# 2_TB6612_3_schdoc.net
KiCad netlist of a schematic drawn in Altium Designer
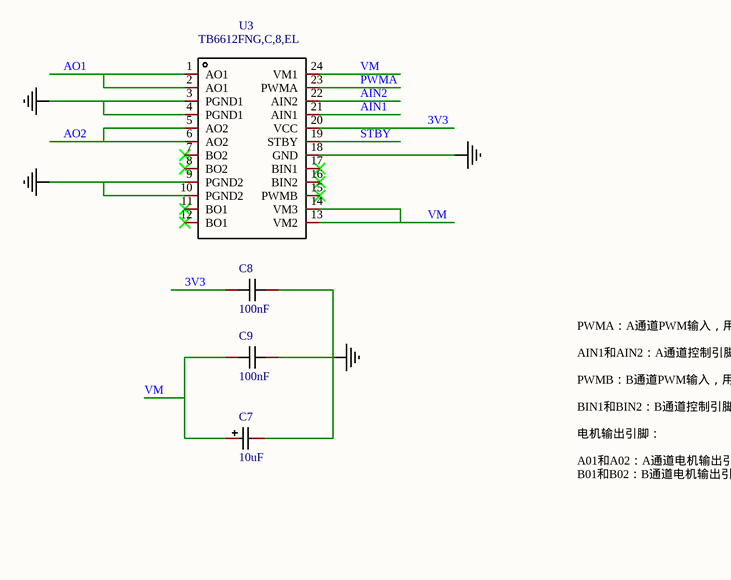
[diagram p0: 2_TB6612（3）.schdoc.schdoc]

(export (version "E")
  (design (tool "Eeschema 10.0.6"))
  (components
    (comp (ref "C7")
      (value "10uF")
      (fields
        (field (name "NAME") "10uF")
        (field (name "MANUFACTURER") "Kyocera AVX")
        (field (name "MANUFACTURER PART") "TAJB106K025RNJ")
        (field (name "TOLERANCE") "±10%")
      )
      (libsource (lib "altium-import") (part "root_2_TAJB106K025RNJ_"))
    )
    (comp (ref "C8")
      (value "100nF")
      (fields (field (name "NAME") "100nF"))
      (libsource (lib "altium-import") (part "root_0_CAP_0603_"))
    )
    (comp (ref "C9")
      (value "100nF")
      (fields (field (name "NAME") "100nF"))
      (libsource (lib "altium-import") (part "root_0_CAP_0603_"))
    )
    (comp (ref "U3")
      (value "TB6612FNG,C,8,EL")
      (description "驱动电机类型:有刷直流电机;电源电压:2.7V~5.5V;输出电流:1A;接口:并行;")
      (fields (field (name "NAME") "TB6612FNG,C,8,EL") (field (name "MANUFACTURER") "TOSHIBA(东芝)"))
      (libsource (lib "altium-import") (part "root_0_TB6612FNG,C,8,EL_"))
    )
  )
  (nets
    (net (code "1") (name "/3V3") (class "Default")
      (node (ref "C8") (pin "1") (pinfunction "1_1") (pintype "passive"))
      (node (ref "U3") (pin "20") (pinfunction "VCC_20") (pintype "passive"))
    )
    (net (code "2") (name "/AIN1") (class "Default")
      (node (ref "U3") (pin "21") (pinfunction "AIN1_21") (pintype "passive"))
    )
    (net (code "3") (name "/AIN2") (class "Default")
      (node (ref "U3") (pin "22") (pinfunction "AIN2_22") (pintype "passive"))
    )
    (net (code "4") (name "/AO1") (class "Default")
      (node (ref "U3") (pin "1") (pinfunction "AO1_1") (pintype "passive"))
      (node (ref "U3") (pin "2") (pinfunction "AO1_2") (pintype "passive"))
    )
    (net (code "5") (name "/AO2") (class "Default")
      (node (ref "U3") (pin "5") (pinfunction "AO2_5") (pintype "passive"))
      (node (ref "U3") (pin "6") (pinfunction "AO2_6") (pintype "passive"))
    )
    (net (code "6") (name "/PWMA") (class "Default")
      (node (ref "U3") (pin "23") (pinfunction "PWMA_23") (pintype "passive"))
    )
    (net (code "7") (name "/STBY") (class "Default")
      (node (ref "U3") (pin "19") (pinfunction "STBY_19") (pintype "passive"))
    )
    (net (code "8") (name "/VM") (class "Default")
      (node (ref "C7") (pin "1") (pinfunction "1_1") (pintype "passive"))
      (node (ref "C9") (pin "1") (pinfunction "1_1") (pintype "passive"))
      (node (ref "U3") (pin "13") (pinfunction "VM2_13") (pintype "passive"))
      (node (ref "U3") (pin "14") (pinfunction "VM3_14") (pintype "passive"))
      (node (ref "U3") (pin "24") (pinfunction "VM1_24") (pintype "passive"))
    )
    (net (code "9") (name "<NO NET>") (class "Default")
      (node (ref "C7") (pin "2") (pinfunction "2_2") (pintype "passive"))
      (node (ref "C8") (pin "2") (pinfunction "2_2") (pintype "passive"))
      (node (ref "C9") (pin "2") (pinfunction "2_2") (pintype "passive"))
      (node (ref "U3") (pin "10") (pinfunction "PGND2_10") (pintype "passive"))
      (node (ref "U3") (pin "18") (pinfunction "GND_18") (pintype "passive"))
      (node (ref "U3") (pin "3") (pinfunction "PGND1_3") (pintype "passive"))
      (node (ref "U3") (pin "4") (pinfunction "PGND1_4") (pintype "passive"))
      (node (ref "U3") (pin "9") (pinfunction "PGND2_9") (pintype "passive"))
    )
    (net (code "10") (name "unconnected-(U3-BIN1-Pad17)") (class "Default")
      (node (ref "U3") (pin "17") (pinfunction "BIN1_17") (pintype "passive+no_connect"))
    )
    (net (code "11") (name "unconnected-(U3-BIN2-Pad16)") (class "Default")
      (node (ref "U3") (pin "16") (pinfunction "BIN2_16") (pintype "passive+no_connect"))
    )
    (net (code "12") (name "unconnected-(U3-BO1-Pad11)") (class "Default")
      (node (ref "U3") (pin "11") (pinfunction "BO1_11") (pintype "passive+no_connect"))
    )
    (net (code "13") (name "unconnected-(U3-BO1-Pad12)") (class "Default")
      (node (ref "U3") (pin "12") (pinfunction "BO1_12") (pintype "passive+no_connect"))
    )
    (net (code "14") (name "unconnected-(U3-BO2-Pad7)") (class "Default")
      (node (ref "U3") (pin "7") (pinfunction "BO2_7") (pintype "passive+no_connect"))
    )
    (net (code "15") (name "unconnected-(U3-BO2-Pad8)") (class "Default")
      (node (ref "U3") (pin "8") (pinfunction "BO2_8") (pintype "passive+no_connect"))
    )
    (net (code "16") (name "unconnected-(U3-PWMB-Pad15)") (class "Default")
      (node (ref "U3") (pin "15") (pinfunction "PWMB_15") (pintype "passive+no_connect"))
    )
  )
)
